# RS232_rev4.net
KiCad netlist of a schematic drawn in EAGLE
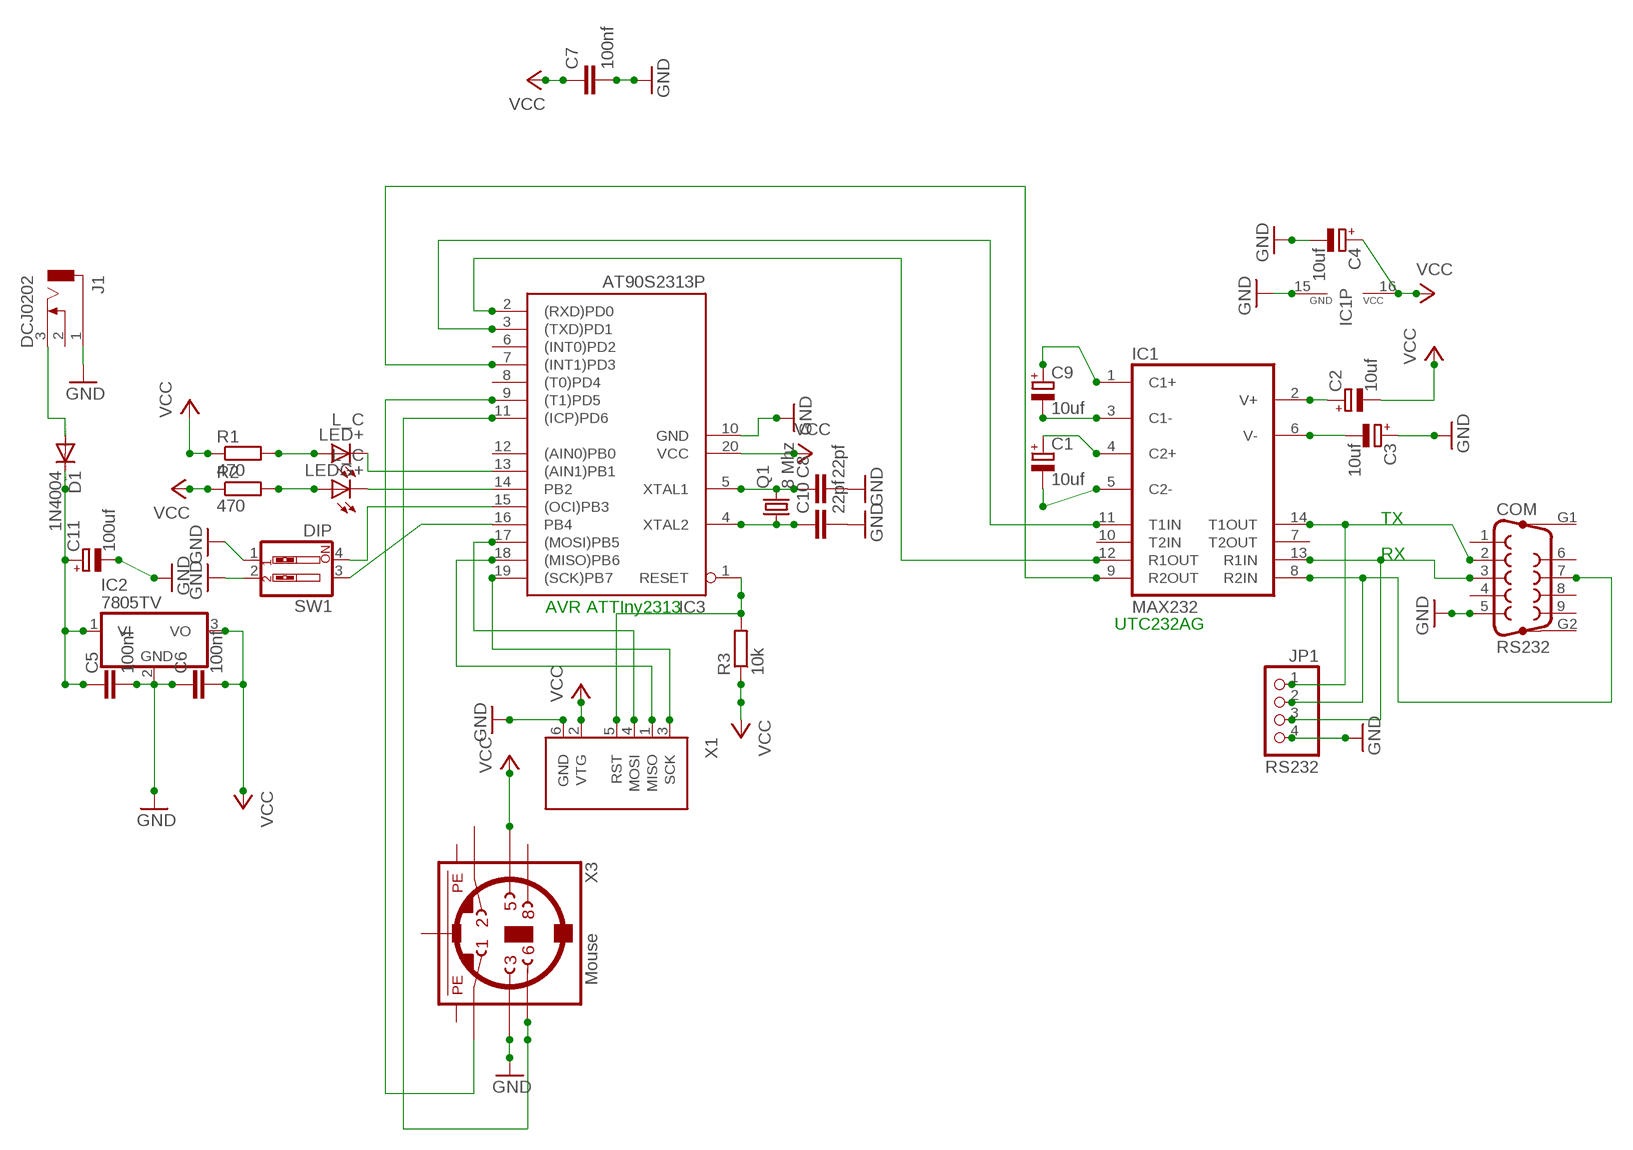
[diagram p0: schematic, sheet 1]

(export (version "E")
  (design (tool "Eeschema 10.0.6"))
  (components
    (comp (ref "C1")
      (value "10uf")
      (footprint "eagle-import:TT2D4")
      (libsource (lib "eagle-import") (part "CPOL-EUTT2D4"))
    )
    (comp (ref "C2")
      (value "10uf")
      (footprint "eagle-import:TT2D4")
      (libsource (lib "eagle-import") (part "CPOL-EUTT2D4"))
    )
    (comp (ref "C3")
      (value "10uf")
      (footprint "eagle-import:TT2D4")
      (libsource (lib "eagle-import") (part "CPOL-EUTT2D4"))
    )
    (comp (ref "C4")
      (value "10uf")
      (footprint "eagle-import:TT2D4")
      (libsource (lib "eagle-import") (part "CPOL-EUTT2D4"))
    )
    (comp (ref "C5")
      (value "100nf")
      (footprint "eagle-import:C1206")
      (libsource (lib "eagle-import") (part "C-EUC1206"))
    )
    (comp (ref "C6")
      (value "100nf")
      (footprint "eagle-import:C1206")
      (libsource (lib "eagle-import") (part "C-EUC1206"))
    )
    (comp (ref "C7")
      (value "100nf")
      (footprint "eagle-import:C1206")
      (libsource (lib "eagle-import") (part "C-EUC1206"))
    )
    (comp (ref "C8")
      (value "22pf")
      (footprint "eagle-import:C1206")
      (libsource (lib "eagle-import") (part "C-EUC1206"))
    )
    (comp (ref "C9")
      (value "10uf")
      (footprint "eagle-import:TT2D4")
      (libsource (lib "eagle-import") (part "CPOL-EUTT2D4"))
    )
    (comp (ref "C10")
      (value "22pf")
      (footprint "eagle-import:C1206")
      (libsource (lib "eagle-import") (part "C-EUC1206"))
    )
    (comp (ref "C11")
      (value "100uf")
      (footprint "eagle-import:TT2D4")
      (libsource (lib "eagle-import") (part "CPOL-EUTT2D4"))
    )
    (comp (ref "COM")
      (value "RS232")
      (footprint "eagle-import:F09HP")
      (libsource (lib "eagle-import") (part "F09HP"))
    )
    (comp (ref "D1")
      (value "1N4004")
      (footprint "eagle-import:DO41-10")
      (libsource (lib "eagle-import") (part "1N4004"))
    )
    (comp (ref "IC1")
      (value "MAX232")
      (footprint "eagle-import:DIL16")
      (fields (field (name "MF") "MAXIM") (field (name "MPN") "MAX232ACPE+"))
      (libsource (lib "eagle-import") (part "MAX232"))
    )
    (comp (ref "IC2")
      (value "7805TV")
      (footprint "eagle-import:TO220V")
      (libsource (lib "eagle-import") (part "78TV05"))
    )
    (comp (ref "IC3")
      (value "AT90S2313P")
      (footprint "eagle-import:DIL20")
      (libsource (lib "eagle-import") (part "AT90S2313P"))
    )
    (comp (ref "J1")
      (value "DCJ0202")
      (footprint "eagle-import:DCJ0202")
      (libsource (lib "eagle-import") (part "DCJ0202"))
    )
    (comp (ref "JP1")
      (value "RS232")
      (footprint "eagle-import:1X04")
      (libsource (lib "eagle-import") (part "PINHD-1X4"))
    )
    (comp (ref "LED+")
      (value "L_C")
      (footprint "eagle-import:LED3MM")
      (libsource (lib "eagle-import") (part "LED3MM"))
    )
    (comp (ref "LEDG+")
      (value "L_C")
      (footprint "eagle-import:LED3MM")
      (libsource (lib "eagle-import") (part "LED3MM"))
    )
    (comp (ref "Q1")
      (value "8 Mhz")
      (footprint "eagle-import:HC49_S")
      (libsource (lib "eagle-import") (part "CRYSTALHC49S"))
    )
    (comp (ref "R1")
      (value "470")
      (footprint "eagle-import:R1206")
      (libsource (lib "eagle-import") (part "R-EU_R1206"))
    )
    (comp (ref "R2")
      (value "470")
      (footprint "eagle-import:R1206")
      (libsource (lib "eagle-import") (part "R-EU_R1206"))
    )
    (comp (ref "R3")
      (value "10k")
      (footprint "eagle-import:R1206")
      (libsource (lib "eagle-import") (part "R-EU_R1206"))
    )
    (comp (ref "SW1")
      (value "DIP")
      (footprint "eagle-import:EDG-02")
      (libsource (lib "eagle-import") (part "SW_DIP-2"))
    )
    (comp (ref "X1")
      (value "AVRISP6PINHEADER")
      (footprint "eagle-import:6PINHEADER")
      (libsource (lib "eagle-import") (part "AVRISP6PINHEADER"))
    )
    (comp (ref "X3")
      (value "Mouse")
      (footprint "eagle-import:M_DIN6")
      (libsource (lib "eagle-import") (part "MINI_DIN_6"))
    )
  )
  (nets
    (net (code "1") (name "/PE1") (class "Default")
      (node (ref "X3") (pin "SH1") (pinfunction "PE1_SH1") (pintype "power_in"))
    )
    (net (code "2") (name "/PE2") (class "Default")
      (node (ref "X3") (pin "SH2") (pinfunction "PE2_SH2") (pintype "power_in"))
    )
    (net (code "3") (name "/PE3") (class "Default")
      (node (ref "X3") (pin "SH3") (pinfunction "PE3_SH3") (pintype "power_in"))
    )
    (net (code "4") (name "GND") (class "Default")
      (node (ref "C10") (pin "2") (pinfunction "2_2") (pintype "passive"))
      (node (ref "C11") (pin "-") (pinfunction "-_-") (pintype "passive"))
      (node (ref "C3") (pin "+") (pinfunction "+_+") (pintype "passive"))
      (node (ref "C4") (pin "-") (pinfunction "-_-") (pintype "passive"))
      (node (ref "C5") (pin "2") (pinfunction "2_2") (pintype "passive"))
      (node (ref "C6") (pin "1") (pinfunction "1_1") (pintype "passive"))
      (node (ref "C7") (pin "2") (pinfunction "2_2") (pintype "passive"))
      (node (ref "C8") (pin "2") (pinfunction "2_2") (pintype "passive"))
      (node (ref "COM") (pin "5") (pinfunction "5_5") (pintype "passive"))
      (node (ref "IC1") (pin "15") (pinfunction "GND_15") (pintype "power_in"))
      (node (ref "IC2") (pin "2") (pinfunction "GND_2") (pintype "passive"))
      (node (ref "IC3") (pin "10") (pinfunction "GND_10") (pintype "power_in"))
      (node (ref "J1") (pin "1") (pinfunction "1_1") (pintype "passive"))
      (node (ref "JP1") (pin "4") (pinfunction "4_4") (pintype "passive"))
      (node (ref "SW1") (pin "1") (pinfunction "1_1") (pintype "passive"))
      (node (ref "SW1") (pin "2") (pinfunction "2_2") (pintype "passive"))
      (node (ref "X1") (pin "6") (pinfunction "GND_6") (pintype "bidirectional"))
      (node (ref "X3") (pin "3") (pinfunction "3_3") (pintype "passive"))
    )
    (net (code "5") (name "Net-(D1-PadA)") (class "Default")
      (node (ref "D1") (pin "A") (pinfunction "A_A") (pintype "passive"))
      (node (ref "J1") (pin "3") (pinfunction "3_3") (pintype "passive"))
    )
    (net (code "6") (name "Net-(IC1A-C1+)") (class "Default")
      (node (ref "C9") (pin "+") (pinfunction "+_+") (pintype "passive"))
      (node (ref "IC1") (pin "1") (pinfunction "C1+_1") (pintype "bidirectional"))
    )
    (net (code "7") (name "Net-(IC1A-C1-)") (class "Default")
      (node (ref "C9") (pin "-") (pinfunction "-_-") (pintype "passive"))
      (node (ref "IC1") (pin "3") (pinfunction "C1-_3") (pintype "bidirectional"))
    )
    (net (code "8") (name "Net-(IC1A-C2+)") (class "Default")
      (node (ref "C1") (pin "+") (pinfunction "+_+") (pintype "passive"))
      (node (ref "IC1") (pin "4") (pinfunction "C2+_4") (pintype "bidirectional"))
    )
    (net (code "9") (name "Net-(IC1A-C2-)") (class "Default")
      (node (ref "C1") (pin "-") (pinfunction "-_-") (pintype "passive"))
      (node (ref "IC1") (pin "5") (pinfunction "C2-_5") (pintype "bidirectional"))
    )
    (net (code "10") (name "Net-(IC1A-R1IN)") (class "Default")
      (node (ref "COM") (pin "3") (pinfunction "3_3") (pintype "passive"))
      (node (ref "IC1") (pin "13") (pinfunction "R1IN_13") (pintype "input"))
      (node (ref "JP1") (pin "3") (pinfunction "3_3") (pintype "passive"))
    )
    (net (code "11") (name "Net-(IC1A-R1OUT)") (class "Default")
      (node (ref "IC1") (pin "12") (pinfunction "R1OUT_12") (pintype "output"))
      (node (ref "IC3") (pin "2") (pinfunction "(RXD)PD0_2") (pintype "bidirectional"))
    )
    (net (code "12") (name "Net-(IC1A-R2IN)") (class "Default")
      (node (ref "COM") (pin "7") (pinfunction "7_7") (pintype "passive"))
      (node (ref "IC1") (pin "8") (pinfunction "R2IN_8") (pintype "input"))
      (node (ref "JP1") (pin "2") (pinfunction "2_2") (pintype "passive"))
    )
    (net (code "13") (name "Net-(IC1A-R2OUT)") (class "Default")
      (node (ref "IC1") (pin "9") (pinfunction "R2OUT_9") (pintype "output"))
      (node (ref "IC3") (pin "7") (pinfunction "(INT1)PD3_7") (pintype "bidirectional"))
    )
    (net (code "14") (name "Net-(IC1A-T1IN)") (class "Default")
      (node (ref "IC1") (pin "11") (pinfunction "T1IN_11") (pintype "input"))
      (node (ref "IC3") (pin "3") (pinfunction "(TXD)PD1_3") (pintype "bidirectional"))
    )
    (net (code "15") (name "Net-(IC1A-T1OUT)") (class "Default")
      (node (ref "COM") (pin "2") (pinfunction "2_2") (pintype "passive"))
      (node (ref "IC1") (pin "14") (pinfunction "T1OUT_14") (pintype "output"))
      (node (ref "JP1") (pin "1") (pinfunction "1_1") (pintype "passive"))
    )
    (net (code "16") (name "Net-(IC1A-V+)") (class "Default")
      (node (ref "C2") (pin "+") (pinfunction "+_+") (pintype "passive"))
      (node (ref "IC1") (pin "2") (pinfunction "V+_2") (pintype "bidirectional"))
    )
    (net (code "17") (name "Net-(IC1A-V-)") (class "Default")
      (node (ref "C3") (pin "-") (pinfunction "-_-") (pintype "passive"))
      (node (ref "IC1") (pin "6") (pinfunction "V-_6") (pintype "bidirectional"))
    )
    (net (code "18") (name "Net-(IC2-VI)") (class "Default")
      (node (ref "C11") (pin "+") (pinfunction "+_+") (pintype "passive"))
      (node (ref "C5") (pin "1") (pinfunction "1_1") (pintype "passive"))
      (node (ref "D1") (pin "C") (pinfunction "C_C") (pintype "passive"))
      (node (ref "IC2") (pin "1") (pinfunction "VI_1") (pintype "input"))
    )
    (net (code "19") (name "Net-(IC3-(AIN1)PB1)") (class "Default")
      (node (ref "IC3") (pin "13") (pinfunction "(AIN1)PB1_13") (pintype "bidirectional"))
      (node (ref "LED+") (pin "K") (pinfunction "C_K") (pintype "passive"))
    )
    (net (code "20") (name "Net-(IC3-(ICP)PD6)") (class "Default")
      (node (ref "IC3") (pin "11") (pinfunction "(ICP)PD6_11") (pintype "bidirectional"))
      (node (ref "X3") (pin "6") (pinfunction "6_6") (pintype "passive"))
    )
    (net (code "21") (name "Net-(IC3-(MISO)PB6)") (class "Default")
      (node (ref "IC3") (pin "18") (pinfunction "(MISO)PB6_18") (pintype "bidirectional"))
      (node (ref "X1") (pin "1") (pinfunction "MISO_1") (pintype "bidirectional"))
    )
    (net (code "22") (name "Net-(IC3-(MOSI)PB5)") (class "Default")
      (node (ref "IC3") (pin "17") (pinfunction "(MOSI)PB5_17") (pintype "bidirectional"))
      (node (ref "X1") (pin "4") (pinfunction "MOSI_4") (pintype "bidirectional"))
    )
    (net (code "23") (name "Net-(IC3-(OCI)PB3)") (class "Default")
      (node (ref "IC3") (pin "15") (pinfunction "(OCI)PB3_15") (pintype "bidirectional"))
      (node (ref "SW1") (pin "4") (pinfunction "4_4") (pintype "passive"))
    )
    (net (code "24") (name "Net-(IC3-(SCK)PB7)") (class "Default")
      (node (ref "IC3") (pin "19") (pinfunction "(SCK)PB7_19") (pintype "bidirectional"))
      (node (ref "X1") (pin "3") (pinfunction "SCK_3") (pintype "bidirectional"))
    )
    (net (code "25") (name "Net-(IC3-(T1)PD5)") (class "Default")
      (node (ref "IC3") (pin "9") (pinfunction "(T1)PD5_9") (pintype "bidirectional"))
      (node (ref "X3") (pin "1") (pinfunction "1_1") (pintype "passive"))
    )
    (net (code "26") (name "Net-(IC3-PB2)") (class "Default")
      (node (ref "IC3") (pin "14") (pinfunction "PB2_14") (pintype "bidirectional"))
      (node (ref "LEDG+") (pin "K") (pinfunction "C_K") (pintype "passive"))
    )
    (net (code "27") (name "Net-(IC3-PB4)") (class "Default")
      (node (ref "IC3") (pin "16") (pinfunction "PB4_16") (pintype "bidirectional"))
      (node (ref "SW1") (pin "3") (pinfunction "3_3") (pintype "passive"))
    )
    (net (code "28") (name "Net-(IC3-RESET)") (class "Default")
      (node (ref "IC3") (pin "1") (pinfunction "RESET_1") (pintype "bidirectional"))
      (node (ref "R3") (pin "2") (pinfunction "2_2") (pintype "passive"))
      (node (ref "X1") (pin "5") (pinfunction "RST_5") (pintype "bidirectional"))
    )
    (net (code "29") (name "Net-(IC3-XTAL1)") (class "Default")
      (node (ref "C8") (pin "1") (pinfunction "1_1") (pintype "passive"))
      (node (ref "IC3") (pin "5") (pinfunction "XTAL1_5") (pintype "bidirectional"))
      (node (ref "Q1") (pin "2") (pinfunction "2_2") (pintype "passive"))
    )
    (net (code "30") (name "Net-(IC3-XTAL2)") (class "Default")
      (node (ref "C10") (pin "1") (pinfunction "1_1") (pintype "passive"))
      (node (ref "IC3") (pin "4") (pinfunction "XTAL2_4") (pintype "bidirectional"))
      (node (ref "Q1") (pin "1") (pinfunction "1_1") (pintype "passive"))
    )
    (net (code "31") (name "Net-(LED+-PadA)") (class "Default")
      (node (ref "LED+") (pin "A") (pinfunction "A_A") (pintype "passive"))
      (node (ref "R1") (pin "2") (pinfunction "2_2") (pintype "passive"))
    )
    (net (code "32") (name "Net-(LEDG+-PadA)") (class "Default")
      (node (ref "LEDG+") (pin "A") (pinfunction "A_A") (pintype "passive"))
      (node (ref "R2") (pin "2") (pinfunction "2_2") (pintype "passive"))
    )
    (net (code "33") (name "VCC") (class "Default")
      (node (ref "C2") (pin "-") (pinfunction "-_-") (pintype "passive"))
      (node (ref "C4") (pin "+") (pinfunction "+_+") (pintype "passive"))
      (node (ref "C6") (pin "2") (pinfunction "2_2") (pintype "passive"))
      (node (ref "C7") (pin "1") (pinfunction "1_1") (pintype "passive"))
      (node (ref "IC1") (pin "16") (pinfunction "VCC_16") (pintype "power_in"))
      (node (ref "IC2") (pin "3") (pinfunction "VO_3") (pintype "passive"))
      (node (ref "IC3") (pin "20") (pinfunction "VCC_20") (pintype "power_in"))
      (node (ref "R1") (pin "1") (pinfunction "1_1") (pintype "passive"))
      (node (ref "R2") (pin "1") (pinfunction "1_1") (pintype "passive"))
      (node (ref "R3") (pin "1") (pinfunction "1_1") (pintype "passive"))
      (node (ref "X1") (pin "2") (pinfunction "VTG_2") (pintype "bidirectional"))
      (node (ref "X3") (pin "5") (pinfunction "5_5") (pintype "passive"))
    )
    (net (code "34") (name "unconnected-(COM-Pad1)") (class "Default")
      (node (ref "COM") (pin "1") (pinfunction "1_1") (pintype "passive"))
    )
    (net (code "35") (name "unconnected-(COM-Pad4)") (class "Default")
      (node (ref "COM") (pin "4") (pinfunction "4_4") (pintype "passive"))
    )
    (net (code "36") (name "unconnected-(COM-Pad6)") (class "Default")
      (node (ref "COM") (pin "6") (pinfunction "6_6") (pintype "passive"))
    )
    (net (code "37") (name "unconnected-(COM-Pad8)") (class "Default")
      (node (ref "COM") (pin "8") (pinfunction "8_8") (pintype "passive"))
    )
    (net (code "38") (name "unconnected-(COM-Pad9)") (class "Default")
      (node (ref "COM") (pin "9") (pinfunction "9_9") (pintype "passive"))
    )
    (net (code "39") (name "unconnected-(COM-PadG1)") (class "Default")
      (node (ref "COM") (pin "G1") (pinfunction "G1_G1") (pintype "passive"))
    )
    (net (code "40") (name "unconnected-(COM-PadG2)") (class "Default")
      (node (ref "COM") (pin "G2") (pinfunction "G2_G2") (pintype "passive"))
    )
    (net (code "41") (name "unconnected-(IC1A-T2IN-Pad10)") (class "Default")
      (node (ref "IC1") (pin "10") (pinfunction "T2IN_10") (pintype "input"))
    )
    (net (code "42") (name "unconnected-(IC1A-T2OUT-Pad7)") (class "Default")
      (node (ref "IC1") (pin "7") (pinfunction "T2OUT_7") (pintype "output"))
    )
    (net (code "43") (name "unconnected-(IC3-(AIN0)PB0-Pad12)") (class "Default")
      (node (ref "IC3") (pin "12") (pinfunction "(AIN0)PB0_12") (pintype "bidirectional"))
    )
    (net (code "44") (name "unconnected-(IC3-(INT0)PD2-Pad6)") (class "Default")
      (node (ref "IC3") (pin "6") (pinfunction "(INT0)PD2_6") (pintype "bidirectional"))
    )
    (net (code "45") (name "unconnected-(IC3-(T0)PD4-Pad8)") (class "Default")
      (node (ref "IC3") (pin "8") (pinfunction "(T0)PD4_8") (pintype "bidirectional"))
    )
    (net (code "46") (name "unconnected-(J1-Pad2)") (class "Default")
      (node (ref "J1") (pin "2") (pinfunction "2_2") (pintype "passive"))
    )
    (net (code "47") (name "unconnected-(X3-Pad2)") (class "Default")
      (node (ref "X3") (pin "2") (pinfunction "2_2") (pintype "passive"))
    )
    (net (code "48") (name "unconnected-(X3-Pad8)") (class "Default")
      (node (ref "X3") (pin "8") (pinfunction "8_8") (pintype "passive"))
    )
  )
)
